# analog_outputs_blk.net
KiCad netlist of a schematic drawn in Altium Designer
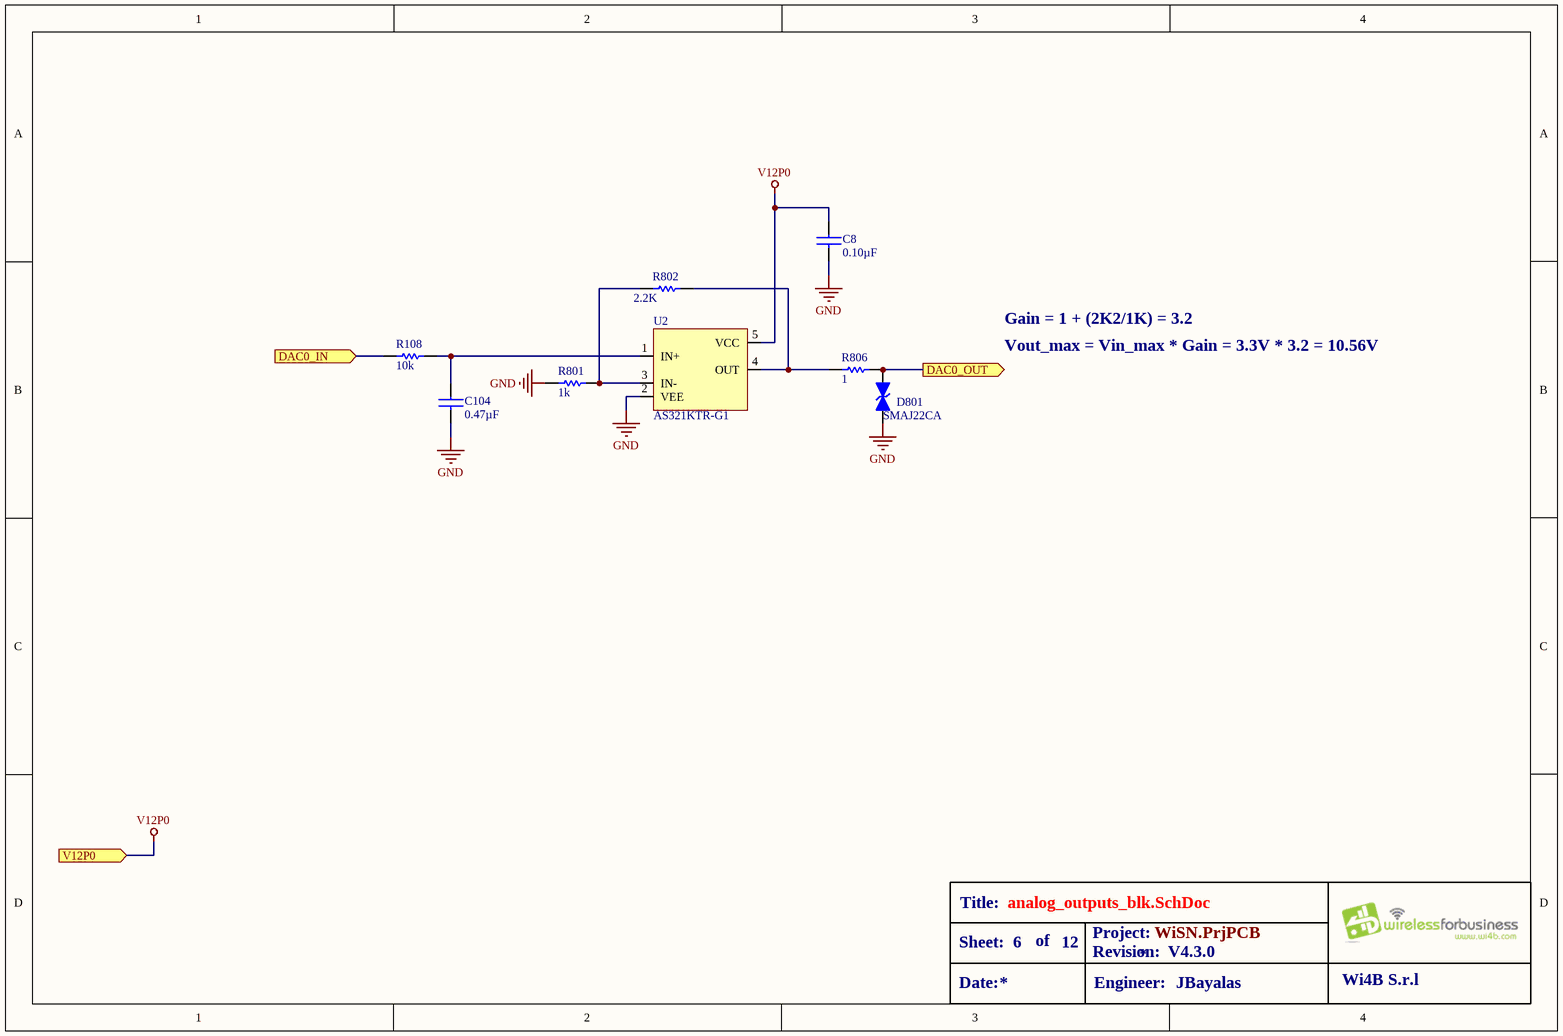
[diagram p0: analog_outputs_blk.SchDoc]

(export (version "E")
  (design (tool "Eeschema 10.0.6"))
  (components
    (comp (ref "C8")
      (value "0.10µF")
      (footprint "C0402")
      (description "CAP CER 0.1UF 50V X7R 0402")
      (fields (field (name "MPN") "GRM155R71H104ME14D"))
      (libsource (lib "Capacitor") (part "GRM155R71H104ME14D"))
    )
    (comp (ref "C104")
      (value "0.47µF")
      (footprint "C0603")
      (description "CAP CER 0.47UF 16V X7R 0603")
      (fields (field (name "MPN") "GRM188R71C474KA88D"))
      (libsource (lib "Capacitor") (part "GRM188R71C474KA88D"))
    )
    (comp (ref "D801")
      (value "SMAJ22CA")
      (footprint "DO-214AC")
      (description "TVS Diodes - Transient Voltage Suppressors 22Vr 400W 11.3A 5% BiDirectional")
      (fields (field (name "MPN") "SMAJ22CA"))
      (libsource (lib "Diode") (part "SMAJ22CA"))
    )
    (comp (ref "R108")
      (value "10k")
      (footprint "R0402")
      (description "RES SMD 10K OHM 1% 1/10W 0402")
      (fields (field (name "MPN") "ERJ-2RKF1002X"))
      (libsource (lib "Res") (part "ERJ-2RKF1002X"))
    )
    (comp (ref "R801")
      (value "1k")
      (footprint "R0402")
      (description "RES SMD 1K OHM 1% 1/10W 0402")
      (fields (field (name "MPN") "ERJ-2RKF1001X"))
      (libsource (lib "Res") (part "ERJ-2RKF1001X"))
    )
    (comp (ref "R802")
      (value "2.2K")
      (footprint "R0603")
      (description "RES SMD 2.2K OHM 1% 1/10W 0603")
      (fields (field (name "MPN") "CRCW06032K20FKEA"))
      (libsource (lib "WiLamp") (part "CRCW06032K20FKEA"))
    )
    (comp (ref "R806")
      (value "1")
      (footprint "R0402")
      (description "RES SMD 1 OHM 1% 1/16W 0402")
      (fields (field (name "MPN") "CRCW04021R00FKED"))
      (libsource (lib "Res") (part "CRCW04021R00FKED"))
    )
    (comp (ref "U2")
      (value "AS321KTR-G1")
      (footprint "SOT-23-5")
      (description "IC OPAMP GP 1 CIRCUIT SOT25")
      (libsource (lib "IC") (part "AS321KTR-G1"))
    )
  )
  (nets
    (net (code "1") (name "/DAC0_IN") (class "Default")
      (node (ref "R108") (pin "1") (pinfunction "1_1") (pintype "passive"))
    )
    (net (code "2") (name "/DAC0_OUT") (class "Default")
      (node (ref "D801") (pin "1") (pinfunction "A_1") (pintype "passive"))
      (node (ref "R806") (pin "2") (pinfunction "2_2") (pintype "passive"))
    )
    (net (code "3") (name "GND") (class "Default")
      (node (ref "C104") (pin "2") (pinfunction "2_2") (pintype "passive"))
      (node (ref "C8") (pin "2") (pinfunction "2_2") (pintype "passive"))
      (node (ref "D801") (pin "2") (pinfunction "K_2") (pintype "passive"))
      (node (ref "R801") (pin "1") (pinfunction "1_1") (pintype "passive"))
      (node (ref "U2") (pin "2") (pinfunction "VEE_2") (pintype "passive"))
    )
    (net (code "4") (name "Net-(U2-IN+)") (class "Default")
      (node (ref "C104") (pin "1") (pinfunction "1_1") (pintype "passive"))
      (node (ref "R108") (pin "2") (pinfunction "2_2") (pintype "passive"))
      (node (ref "U2") (pin "1") (pinfunction "IN+_1") (pintype "passive"))
    )
    (net (code "5") (name "Net-(U2-IN-)") (class "Default")
      (node (ref "R801") (pin "2") (pinfunction "2_2") (pintype "passive"))
      (node (ref "R802") (pin "1") (pinfunction "1_1") (pintype "passive"))
      (node (ref "U2") (pin "3") (pinfunction "IN-_3") (pintype "passive"))
    )
    (net (code "6") (name "Net-(U2-OUT)") (class "Default")
      (node (ref "R802") (pin "2") (pinfunction "2_2") (pintype "passive"))
      (node (ref "R806") (pin "1") (pinfunction "1_1") (pintype "passive"))
      (node (ref "U2") (pin "4") (pinfunction "OUT_4") (pintype "passive"))
    )
    (net (code "7") (name "V12P0") (class "Default")
      (node (ref "C8") (pin "1") (pinfunction "1_1") (pintype "passive"))
      (node (ref "U2") (pin "5") (pinfunction "VCC_5") (pintype "passive"))
    )
  )
)
